# schema_mpb_1_1_COM.net
KiCad netlist of a schematic drawn in EAGLE
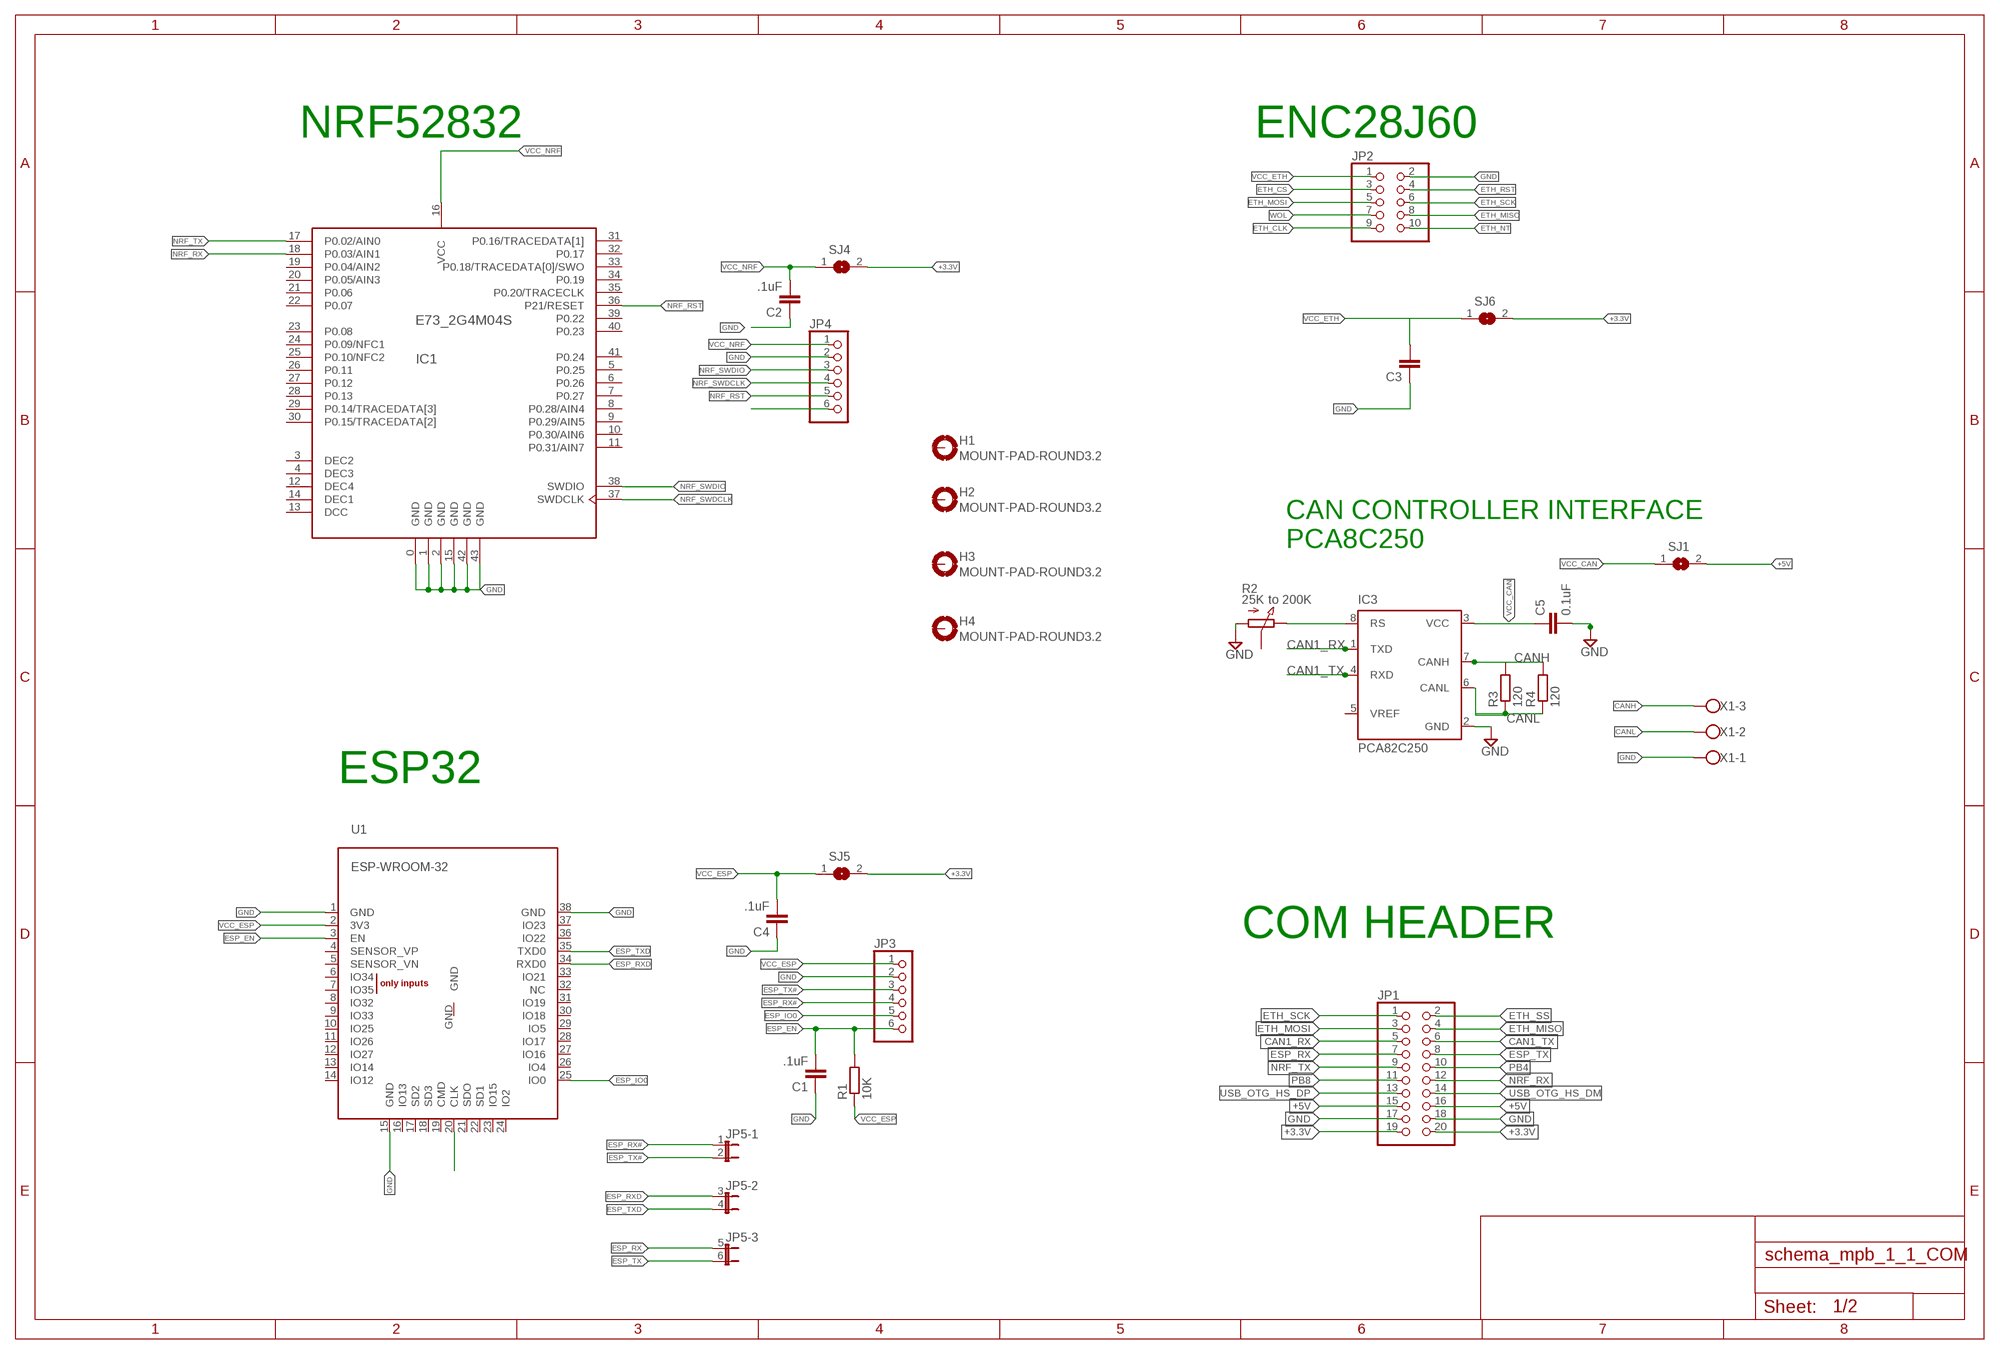
[diagram p0: schematic, sheet 1]

(export (version "E")
  (design (tool "Eeschema 10.0.6"))
  (components
    (comp (ref "C1")
      (value ".1uF")
      (footprint "eagle-import:C0603")
      (libsource (lib "eagle-import") (part "C-EUC0603"))
    )
    (comp (ref "C2")
      (value ".1uF")
      (footprint "eagle-import:C0603")
      (libsource (lib "eagle-import") (part "C-EUC0603"))
    )
    (comp (ref "C3")
      (value "C-EUC0603")
      (footprint "eagle-import:C0603")
      (libsource (lib "eagle-import") (part "C-EUC0603"))
    )
    (comp (ref "C4")
      (value ".1uF")
      (footprint "eagle-import:C0603")
      (libsource (lib "eagle-import") (part "C-EUC0603"))
    )
    (comp (ref "C5")
      (value "0.1uF")
      (footprint "eagle-import:C0805")
      (libsource (lib "eagle-import") (part "C-EUC0805"))
    )
    (comp (ref "H1")
      (value "MOUNT-PAD-ROUND3.2")
      (footprint "eagle-import:3,2-PAD")
      (libsource (lib "eagle-import") (part "MOUNT-PAD-ROUND3.2"))
    )
    (comp (ref "H2")
      (value "MOUNT-PAD-ROUND3.2")
      (footprint "eagle-import:3,2-PAD")
      (libsource (lib "eagle-import") (part "MOUNT-PAD-ROUND3.2"))
    )
    (comp (ref "H3")
      (value "MOUNT-PAD-ROUND3.2")
      (footprint "eagle-import:3,2-PAD")
      (libsource (lib "eagle-import") (part "MOUNT-PAD-ROUND3.2"))
    )
    (comp (ref "H4")
      (value "MOUNT-PAD-ROUND3.2")
      (footprint "eagle-import:3,2-PAD")
      (libsource (lib "eagle-import") (part "MOUNT-PAD-ROUND3.2"))
    )
    (comp (ref "IC1")
      (value "E73_2G4M04S")
      (footprint "eagle-import:E73_2G4M04S")
      (libsource (lib "eagle-import") (part "E73_2G4M04S"))
    )
    (comp (ref "IC3")
      (value "PCA82C250")
      (footprint "eagle-import:DIL08")
      (libsource (lib "eagle-import") (part "PCA82C250"))
    )
    (comp (ref "JP1")
      (value "PINHD-2X10")
      (footprint "eagle-import:2X10")
      (libsource (lib "eagle-import") (part "PINHD-2X10"))
    )
    (comp (ref "JP2")
      (value "PINHD-2X5")
      (footprint "eagle-import:2X05")
      (libsource (lib "eagle-import") (part "PINHD-2X5"))
    )
    (comp (ref "JP3")
      (value "PINHD-1X6")
      (footprint "eagle-import:1X06")
      (libsource (lib "eagle-import") (part "PINHD-1X6"))
    )
    (comp (ref "JP4")
      (value "PINHD-1X6")
      (footprint "eagle-import:1X06")
      (libsource (lib "eagle-import") (part "PINHD-1X6"))
    )
    (comp (ref "JP5")
      (value "JP3QE")
      (footprint "eagle-import:JP3Q")
      (libsource (lib "eagle-import") (part "JP3QE"))
    )
    (comp (ref "R1")
      (value "10K")
      (footprint "eagle-import:R0603")
      (libsource (lib "eagle-import") (part "R-EU_R0603"))
    )
    (comp (ref "R2")
      (value "25K to 200K")
      (footprint "eagle-import:PC25")
      (fields (field (name "MF") "CLAROSTAT") (field (name "MPN") "308NPC25KS"))
      (libsource (lib "eagle-import") (part "PC25"))
    )
    (comp (ref "R3")
      (value "120")
      (footprint "eagle-import:R0805")
      (libsource (lib "eagle-import") (part "R-EU_R0805"))
    )
    (comp (ref "R4")
      (value "120")
      (footprint "eagle-import:R0805")
      (libsource (lib "eagle-import") (part "R-EU_R0805"))
    )
    (comp (ref "SJ1")
      (value "SJW")
      (footprint "eagle-import:SJW")
      (libsource (lib "eagle-import") (part "SJW"))
    )
    (comp (ref "SJ4")
      (value "SJW")
      (footprint "eagle-import:SJW")
      (libsource (lib "eagle-import") (part "SJW"))
    )
    (comp (ref "SJ5")
      (value "SJW")
      (footprint "eagle-import:SJW")
      (libsource (lib "eagle-import") (part "SJW"))
    )
    (comp (ref "SJ6")
      (value "SJW")
      (footprint "eagle-import:SJW")
      (libsource (lib "eagle-import") (part "SJW"))
    )
    (comp (ref "U1")
      (value "ESP-WROOM-32")
      (footprint "eagle-import:ESP-WROOM-32")
      (libsource (lib "eagle-import") (part "ESP-WROOM-32"))
    )
    (comp (ref "X1")
      (value "W237-103")
      (footprint "eagle-import:W237-103")
      (fields (field (name "MPN") "237-103"))
      (libsource (lib "eagle-import") (part "W237-103"))
    )
  )
  (nets
    (net (code "1") (name "+3.3V") (class "Default")
      (node (ref "JP1") (pin "19") (pinfunction "19_19") (pintype "passive"))
      (node (ref "JP1") (pin "20") (pinfunction "20_20") (pintype "passive"))
      (node (ref "SJ4") (pin "2") (pinfunction "2_2") (pintype "passive"))
      (node (ref "SJ5") (pin "2") (pinfunction "2_2") (pintype "passive"))
      (node (ref "SJ6") (pin "2") (pinfunction "2_2") (pintype "passive"))
    )
    (net (code "2") (name "+5V") (class "Default")
      (node (ref "JP1") (pin "15") (pinfunction "15_15") (pintype "passive"))
      (node (ref "JP1") (pin "16") (pinfunction "16_16") (pintype "passive"))
      (node (ref "SJ1") (pin "2") (pinfunction "2_2") (pintype "passive"))
    )
    (net (code "3") (name "CAN1_RX") (class "Default")
      (node (ref "IC3") (pin "1") (pinfunction "TXD_1") (pintype "input"))
      (node (ref "JP1") (pin "5") (pinfunction "5_5") (pintype "passive"))
    )
    (net (code "4") (name "CAN1_TX") (class "Default")
      (node (ref "IC3") (pin "4") (pinfunction "RXD_4") (pintype "output"))
      (node (ref "JP1") (pin "6") (pinfunction "6_6") (pintype "passive"))
    )
    (net (code "5") (name "CANH") (class "Default")
      (node (ref "IC3") (pin "7") (pinfunction "CANH_7") (pintype "bidirectional"))
      (node (ref "R3") (pin "2") (pinfunction "2_2") (pintype "passive"))
      (node (ref "R4") (pin "2") (pinfunction "2_2") (pintype "passive"))
      (node (ref "X1") (pin "3") (pinfunction "KL_3") (pintype "passive"))
    )
    (net (code "6") (name "CANL") (class "Default")
      (node (ref "IC3") (pin "6") (pinfunction "CANL_6") (pintype "bidirectional"))
      (node (ref "R3") (pin "1") (pinfunction "1_1") (pintype "passive"))
      (node (ref "R4") (pin "1") (pinfunction "1_1") (pintype "passive"))
      (node (ref "X1") (pin "2") (pinfunction "KL_2") (pintype "passive"))
    )
    (net (code "7") (name "DCC") (class "Default")
      (node (ref "IC1") (pin "13") (pinfunction "DCC_13") (pintype "power_in"))
    )
    (net (code "8") (name "DEC1") (class "Default")
      (node (ref "IC1") (pin "14") (pinfunction "DEC1_14") (pintype "power_in"))
    )
    (net (code "9") (name "DEC2") (class "Default")
      (node (ref "IC1") (pin "3") (pinfunction "DEC2_3") (pintype "power_in"))
    )
    (net (code "10") (name "DEC3") (class "Default")
      (node (ref "IC1") (pin "4") (pinfunction "DEC3_4") (pintype "power_in"))
    )
    (net (code "11") (name "DEC4") (class "Default")
      (node (ref "IC1") (pin "12") (pinfunction "DEC4_12") (pintype "power_in"))
    )
    (net (code "12") (name "ESP_EN") (class "Default")
      (node (ref "C1") (pin "2") (pinfunction "2_2") (pintype "passive"))
      (node (ref "JP3") (pin "6") (pinfunction "6_6") (pintype "passive"))
      (node (ref "R1") (pin "2") (pinfunction "2_2") (pintype "passive"))
      (node (ref "U1") (pin "3") (pinfunction "EN_3") (pintype "bidirectional"))
    )
    (net (code "13") (name "ESP_IO0") (class "Default")
      (node (ref "JP3") (pin "5") (pinfunction "5_5") (pintype "passive"))
      (node (ref "U1") (pin "25") (pinfunction "IO0_25") (pintype "bidirectional"))
    )
    (net (code "14") (name "ESP_RX") (class "Default")
      (node (ref "JP1") (pin "7") (pinfunction "7_7") (pintype "passive"))
      (node (ref "JP5") (pin "5") (pinfunction "1_5") (pintype "passive"))
    )
    (net (code "15") (name "ESP_RX#") (class "Default")
      (node (ref "JP3") (pin "4") (pinfunction "4_4") (pintype "passive"))
      (node (ref "JP5") (pin "1") (pinfunction "1_1") (pintype "passive"))
    )
    (net (code "16") (name "ESP_RXD") (class "Default")
      (node (ref "JP5") (pin "3") (pinfunction "1_3") (pintype "passive"))
      (node (ref "U1") (pin "34") (pinfunction "RXD0_34") (pintype "bidirectional"))
    )
    (net (code "17") (name "ESP_TX") (class "Default")
      (node (ref "JP1") (pin "8") (pinfunction "8_8") (pintype "passive"))
      (node (ref "JP5") (pin "6") (pinfunction "2_6") (pintype "passive"))
    )
    (net (code "18") (name "ESP_TX#") (class "Default")
      (node (ref "JP3") (pin "3") (pinfunction "3_3") (pintype "passive"))
      (node (ref "JP5") (pin "2") (pinfunction "2_2") (pintype "passive"))
    )
    (net (code "19") (name "ESP_TXD") (class "Default")
      (node (ref "JP5") (pin "4") (pinfunction "2_4") (pintype "passive"))
      (node (ref "U1") (pin "35") (pinfunction "TXD0_35") (pintype "bidirectional"))
    )
    (net (code "20") (name "ETH_CLK") (class "Default")
      (node (ref "JP2") (pin "9") (pinfunction "9_9") (pintype "passive"))
    )
    (net (code "21") (name "ETH_CS") (class "Default")
      (node (ref "JP2") (pin "3") (pinfunction "3_3") (pintype "passive"))
    )
    (net (code "22") (name "ETH_MISO") (class "Default")
      (node (ref "JP1") (pin "4") (pinfunction "4_4") (pintype "passive"))
      (node (ref "JP2") (pin "8") (pinfunction "8_8") (pintype "passive"))
    )
    (net (code "23") (name "ETH_MOSI") (class "Default")
      (node (ref "JP1") (pin "3") (pinfunction "3_3") (pintype "passive"))
      (node (ref "JP2") (pin "5") (pinfunction "5_5") (pintype "passive"))
    )
    (net (code "24") (name "ETH_NT") (class "Default")
      (node (ref "JP2") (pin "10") (pinfunction "10_10") (pintype "passive"))
    )
    (net (code "25") (name "ETH_RST") (class "Default")
      (node (ref "JP2") (pin "4") (pinfunction "4_4") (pintype "passive"))
    )
    (net (code "26") (name "ETH_SCK") (class "Default")
      (node (ref "JP1") (pin "1") (pinfunction "1_1") (pintype "passive"))
      (node (ref "JP2") (pin "6") (pinfunction "6_6") (pintype "passive"))
    )
    (net (code "27") (name "ETH_SS") (class "Default")
      (node (ref "JP1") (pin "2") (pinfunction "2_2") (pintype "passive"))
    )
    (net (code "28") (name "GND") (class "Default")
      (node (ref "C1") (pin "1") (pinfunction "1_1") (pintype "passive"))
      (node (ref "C2") (pin "1") (pinfunction "1_1") (pintype "passive"))
      (node (ref "C3") (pin "1") (pinfunction "1_1") (pintype "passive"))
      (node (ref "C4") (pin "1") (pinfunction "1_1") (pintype "passive"))
      (node (ref "C5") (pin "2") (pinfunction "2_2") (pintype "passive"))
      (node (ref "IC1") (pin "0") (pinfunction "GND_0") (pintype "bidirectional"))
      (node (ref "IC1") (pin "1") (pinfunction "GND_1") (pintype "bidirectional"))
      (node (ref "IC1") (pin "15") (pinfunction "GND_15") (pintype "bidirectional"))
      (node (ref "IC1") (pin "2") (pinfunction "GND_2") (pintype "bidirectional"))
      (node (ref "IC1") (pin "42") (pinfunction "GND_42") (pintype "bidirectional"))
      (node (ref "IC1") (pin "43") (pinfunction "GND_43") (pintype "bidirectional"))
      (node (ref "IC3") (pin "2") (pinfunction "GND_2") (pintype "power_in"))
      (node (ref "JP1") (pin "17") (pinfunction "17_17") (pintype "passive"))
      (node (ref "JP1") (pin "18") (pinfunction "18_18") (pintype "passive"))
      (node (ref "JP2") (pin "2") (pinfunction "2_2") (pintype "passive"))
      (node (ref "JP3") (pin "2") (pinfunction "2_2") (pintype "passive"))
      (node (ref "JP4") (pin "2") (pinfunction "2_2") (pintype "passive"))
      (node (ref "R2") (pin "A") (pinfunction "A_A") (pintype "passive"))
      (node (ref "U1") (pin "1") (pinfunction "GND_1") (pintype "bidirectional"))
      (node (ref "U1") (pin "15") (pinfunction "GND_15") (pintype "bidirectional"))
      (node (ref "U1") (pin "38") (pinfunction "GND_38") (pintype "bidirectional"))
      (node (ref "X1") (pin "1") (pinfunction "KL_1") (pintype "passive"))
    )
    (net (code "29") (name "NRF_RST") (class "Default")
      (node (ref "IC1") (pin "36") (pinfunction "P21/RESET_36") (pintype "bidirectional"))
      (node (ref "JP4") (pin "5") (pinfunction "5_5") (pintype "passive"))
    )
    (net (code "30") (name "NRF_RX") (class "Default")
      (node (ref "IC1") (pin "18") (pinfunction "P0.03/AIN1_18") (pintype "bidirectional"))
      (node (ref "JP1") (pin "12") (pinfunction "12_12") (pintype "passive"))
    )
    (net (code "31") (name "NRF_SWDCLK") (class "Default")
      (node (ref "IC1") (pin "37") (pinfunction "SWDCLK_37") (pintype "input"))
      (node (ref "JP4") (pin "4") (pinfunction "4_4") (pintype "passive"))
    )
    (net (code "32") (name "NRF_SWDIO") (class "Default")
      (node (ref "IC1") (pin "38") (pinfunction "SWDIO_38") (pintype "bidirectional"))
      (node (ref "JP4") (pin "3") (pinfunction "3_3") (pintype "passive"))
    )
    (net (code "33") (name "NRF_TX") (class "Default")
      (node (ref "IC1") (pin "17") (pinfunction "P0.02/AIN0_17") (pintype "bidirectional"))
      (node (ref "JP1") (pin "9") (pinfunction "9_9") (pintype "passive"))
    )
    (net (code "34") (name "Net-(IC3-RS)") (class "Default")
      (node (ref "IC3") (pin "8") (pinfunction "RS_8") (pintype "input"))
      (node (ref "R2") (pin "E") (pinfunction "E_E") (pintype "passive"))
    )
    (net (code "35") (name "PB4") (class "Default")
      (node (ref "JP1") (pin "10") (pinfunction "10_10") (pintype "passive"))
    )
    (net (code "36") (name "PB8") (class "Default")
      (node (ref "JP1") (pin "11") (pinfunction "11_11") (pintype "passive"))
    )
    (net (code "37") (name "USB_OTG_HS_DM") (class "Default")
      (node (ref "JP1") (pin "14") (pinfunction "14_14") (pintype "passive"))
    )
    (net (code "38") (name "USB_OTG_HS_DP") (class "Default")
      (node (ref "JP1") (pin "13") (pinfunction "13_13") (pintype "passive"))
    )
    (net (code "39") (name "VCC_CAN") (class "Default")
      (node (ref "C5") (pin "1") (pinfunction "1_1") (pintype "passive"))
      (node (ref "IC3") (pin "3") (pinfunction "VCC_3") (pintype "power_in"))
      (node (ref "SJ1") (pin "1") (pinfunction "1_1") (pintype "passive"))
    )
    (net (code "40") (name "VCC_ESP") (class "Default")
      (node (ref "C4") (pin "2") (pinfunction "2_2") (pintype "passive"))
      (node (ref "JP3") (pin "1") (pinfunction "1_1") (pintype "passive"))
      (node (ref "R1") (pin "1") (pinfunction "1_1") (pintype "passive"))
      (node (ref "SJ5") (pin "1") (pinfunction "1_1") (pintype "passive"))
      (node (ref "U1") (pin "2") (pinfunction "3V3_2") (pintype "bidirectional"))
    )
    (net (code "41") (name "VCC_ETH") (class "Default")
      (node (ref "C3") (pin "2") (pinfunction "2_2") (pintype "passive"))
      (node (ref "JP2") (pin "1") (pinfunction "1_1") (pintype "passive"))
      (node (ref "SJ6") (pin "1") (pinfunction "1_1") (pintype "passive"))
    )
    (net (code "42") (name "VCC_NRF") (class "Default")
      (node (ref "C2") (pin "2") (pinfunction "2_2") (pintype "passive"))
      (node (ref "IC1") (pin "16") (pinfunction "VCC_16") (pintype "passive"))
      (node (ref "JP4") (pin "1") (pinfunction "1_1") (pintype "passive"))
      (node (ref "SJ4") (pin "1") (pinfunction "1_1") (pintype "passive"))
    )
    (net (code "43") (name "WOL") (class "Default")
      (node (ref "JP2") (pin "7") (pinfunction "7_7") (pintype "passive"))
    )
    (net (code "44") (name "unconnected-(H1-MOUNT-PadB3,2)") (class "Default")
      (node (ref "H1") (pin "B3,2") (pinfunction "MOUNT_B3,2") (pintype "passive"))
    )
    (net (code "45") (name "unconnected-(H2-MOUNT-PadB3,2)") (class "Default")
      (node (ref "H2") (pin "B3,2") (pinfunction "MOUNT_B3,2") (pintype "passive"))
    )
    (net (code "46") (name "unconnected-(H3-MOUNT-PadB3,2)") (class "Default")
      (node (ref "H3") (pin "B3,2") (pinfunction "MOUNT_B3,2") (pintype "passive"))
    )
    (net (code "47") (name "unconnected-(H4-MOUNT-PadB3,2)") (class "Default")
      (node (ref "H4") (pin "B3,2") (pinfunction "MOUNT_B3,2") (pintype "passive"))
    )
    (net (code "48") (name "unconnected-(IC1-P0.04{slash}AIN2-Pad19)") (class "Default")
      (node (ref "IC1") (pin "19") (pinfunction "P0.04/AIN2_19") (pintype "bidirectional"))
    )
    (net (code "49") (name "unconnected-(IC1-P0.05{slash}AIN3-Pad20)") (class "Default")
      (node (ref "IC1") (pin "20") (pinfunction "P0.05/AIN3_20") (pintype "bidirectional"))
    )
    (net (code "50") (name "unconnected-(IC1-P0.06-Pad21)") (class "Default")
      (node (ref "IC1") (pin "21") (pinfunction "P0.06_21") (pintype "bidirectional"))
    )
    (net (code "51") (name "unconnected-(IC1-P0.07-Pad22)") (class "Default")
      (node (ref "IC1") (pin "22") (pinfunction "P0.07_22") (pintype "bidirectional"))
    )
    (net (code "52") (name "unconnected-(IC1-P0.08-Pad23)") (class "Default")
      (node (ref "IC1") (pin "23") (pinfunction "P0.08_23") (pintype "bidirectional"))
    )
    (net (code "53") (name "unconnected-(IC1-P0.09{slash}NFC1-Pad24)") (class "Default")
      (node (ref "IC1") (pin "24") (pinfunction "P0.09/NFC1_24") (pintype "bidirectional"))
    )
    (net (code "54") (name "unconnected-(IC1-P0.10{slash}NFC2-Pad25)") (class "Default")
      (node (ref "IC1") (pin "25") (pinfunction "P0.10/NFC2_25") (pintype "bidirectional"))
    )
    (net (code "55") (name "unconnected-(IC1-P0.11-Pad26)") (class "Default")
      (node (ref "IC1") (pin "26") (pinfunction "P0.11_26") (pintype "bidirectional"))
    )
    (net (code "56") (name "unconnected-(IC1-P0.12-Pad27)") (class "Default")
      (node (ref "IC1") (pin "27") (pinfunction "P0.12_27") (pintype "bidirectional"))
    )
    (net (code "57") (name "unconnected-(IC1-P0.13-Pad28)") (class "Default")
      (node (ref "IC1") (pin "28") (pinfunction "P0.13_28") (pintype "bidirectional"))
    )
    (net (code "58") (name "unconnected-(IC1-P0.14{slash}TRACEDATA[3]-Pad29)") (class "Default")
      (node (ref "IC1") (pin "29") (pinfunction "P0.14/TRACEDATA[3]_29") (pintype "bidirectional"))
    )
    (net (code "59") (name "unconnected-(IC1-P0.15{slash}TRACEDATA[2]-Pad30)") (class "Default")
      (node (ref "IC1") (pin "30") (pinfunction "P0.15/TRACEDATA[2]_30") (pintype "bidirectional"))
    )
    (net (code "60") (name "unconnected-(IC1-P0.16{slash}TRACEDATA[1]-Pad31)") (class "Default")
      (node (ref "IC1") (pin "31") (pinfunction "P0.16/TRACEDATA[1]_31") (pintype "bidirectional"))
    )
    (net (code "61") (name "unconnected-(IC1-P0.17-Pad32)") (class "Default")
      (node (ref "IC1") (pin "32") (pinfunction "P0.17_32") (pintype "bidirectional"))
    )
    (net (code "62") (name "unconnected-(IC1-P0.18{slash}TRACEDATA[0]{slash}SWO-Pad33)") (class "Default")
      (node (ref "IC1") (pin "33") (pinfunction "P0.18/TRACEDATA[0]/SWO_33") (pintype "bidirectional"))
    )
    (net (code "63") (name "unconnected-(IC1-P0.19-Pad34)") (class "Default")
      (node (ref "IC1") (pin "34") (pinfunction "P0.19_34") (pintype "bidirectional"))
    )
    (net (code "64") (name "unconnected-(IC1-P0.20{slash}TRACECLK-Pad35)") (class "Default")
      (node (ref "IC1") (pin "35") (pinfunction "P0.20/TRACECLK_35") (pintype "bidirectional"))
    )
    (net (code "65") (name "unconnected-(IC1-P0.22-Pad39)") (class "Default")
      (node (ref "IC1") (pin "39") (pinfunction "P0.22_39") (pintype "bidirectional"))
    )
    (net (code "66") (name "unconnected-(IC1-P0.23-Pad40)") (class "Default")
      (node (ref "IC1") (pin "40") (pinfunction "P0.23_40") (pintype "bidirectional"))
    )
    (net (code "67") (name "unconnected-(IC1-P0.24-Pad41)") (class "Default")
      (node (ref "IC1") (pin "41") (pinfunction "P0.24_41") (pintype "bidirectional"))
    )
    (net (code "68") (name "unconnected-(IC1-P0.25-Pad5)") (class "Default")
      (node (ref "IC1") (pin "5") (pinfunction "P0.25_5") (pintype "bidirectional"))
    )
    (net (code "69") (name "unconnected-(IC1-P0.26-Pad6)") (class "Default")
      (node (ref "IC1") (pin "6") (pinfunction "P0.26_6") (pintype "bidirectional"))
    )
    (net (code "70") (name "unconnected-(IC1-P0.27-Pad7)") (class "Default")
      (node (ref "IC1") (pin "7") (pinfunction "P0.27_7") (pintype "bidirectional"))
    )
    (net (code "71") (name "unconnected-(IC1-P0.28{slash}AIN4-Pad8)") (class "Default")
      (node (ref "IC1") (pin "8") (pinfunction "P0.28/AIN4_8") (pintype "bidirectional"))
    )
    (net (code "72") (name "unconnected-(IC1-P0.29{slash}AIN5-Pad9)") (class "Default")
      (node (ref "IC1") (pin "9") (pinfunction "P0.29/AIN5_9") (pintype "bidirectional"))
    )
    (net (code "73") (name "unconnected-(IC1-P0.30{slash}AIN6-Pad10)") (class "Default")
      (node (ref "IC1") (pin "10") (pinfunction "P0.30/AIN6_10") (pintype "bidirectional"))
    )
    (net (code "74") (name "unconnected-(IC1-P0.31{slash}AIN7-Pad11)") (class "Default")
      (node (ref "IC1") (pin "11") (pinfunction "P0.31/AIN7_11") (pintype "bidirectional"))
    )
    (net (code "75") (name "unconnected-(IC3-VREF-Pad5)") (class "Default")
      (node (ref "IC3") (pin "5") (pinfunction "VREF_5") (pintype "output"))
    )
    (net (code "76") (name "unconnected-(JP4-Pad6)") (class "Default")
      (node (ref "JP4") (pin "6") (pinfunction "6_6") (pintype "passive"))
    )
    (net (code "77") (name "unconnected-(R2-PadS)") (class "Default")
      (node (ref "R2") (pin "S") (pinfunction "S_S") (pintype "passive"))
    )
    (net (code "78") (name "unconnected-(U1-CLK-Pad20)") (class "Default")
      (node (ref "U1") (pin "20") (pinfunction "CLK_20") (pintype "bidirectional"))
    )
    (net (code "79") (name "unconnected-(U1-CMD-Pad19)") (class "Default")
      (node (ref "U1") (pin "19") (pinfunction "CMD_19") (pintype "bidirectional"))
    )
    (net (code "80") (name "unconnected-(U1-IO2-Pad24)") (class "Default")
      (node (ref "U1") (pin "24") (pinfunction "IO2_24") (pintype "bidirectional"))
    )
    (net (code "81") (name "unconnected-(U1-IO4-Pad26)") (class "Default")
      (node (ref "U1") (pin "26") (pinfunction "IO4_26") (pintype "bidirectional"))
    )
    (net (code "82") (name "unconnected-(U1-IO5-Pad29)") (class "Default")
      (node (ref "U1") (pin "29") (pinfunction "IO5_29") (pintype "bidirectional"))
    )
    (net (code "83") (name "unconnected-(U1-IO12-Pad14)") (class "Default")
      (node (ref "U1") (pin "14") (pinfunction "IO12_14") (pintype "bidirectional"))
    )
    (net (code "84") (name "unconnected-(U1-IO13-Pad16)") (class "Default")
      (node (ref "U1") (pin "16") (pinfunction "IO13_16") (pintype "bidirectional"))
    )
    (net (code "85") (name "unconnected-(U1-IO14-Pad13)") (class "Default")
      (node (ref "U1") (pin "13") (pinfunction "IO14_13") (pintype "bidirectional"))
    )
    (net (code "86") (name "unconnected-(U1-IO15-Pad23)") (class "Default")
      (node (ref "U1") (pin "23") (pinfunction "IO15_23") (pintype "bidirectional"))
    )
    (net (code "87") (name "unconnected-(U1-IO16-Pad27)") (class "Default")
      (node (ref "U1") (pin "27") (pinfunction "IO16_27") (pintype "bidirectional"))
    )
    (net (code "88") (name "unconnected-(U1-IO17-Pad28)") (class "Default")
      (node (ref "U1") (pin "28") (pinfunction "IO17_28") (pintype "bidirectional"))
    )
    (net (code "89") (name "unconnected-(U1-IO18-Pad30)") (class "Default")
      (node (ref "U1") (pin "30") (pinfunction "IO18_30") (pintype "bidirectional"))
    )
    (net (code "90") (name "unconnected-(U1-IO19-Pad31)") (class "Default")
      (node (ref "U1") (pin "31") (pinfunction "IO19_31") (pintype "bidirectional"))
    )
    (net (code "91") (name "unconnected-(U1-IO21-Pad33)") (class "Default")
      (node (ref "U1") (pin "33") (pinfunction "IO21_33") (pintype "bidirectional"))
    )
    (net (code "92") (name "unconnected-(U1-IO22-Pad36)") (class "Default")
      (node (ref "U1") (pin "36") (pinfunction "IO22_36") (pintype "bidirectional"))
    )
    (net (code "93") (name "unconnected-(U1-IO23-Pad37)") (class "Default")
      (node (ref "U1") (pin "37") (pinfunction "IO23_37") (pintype "bidirectional"))
    )
    (net (code "94") (name "unconnected-(U1-IO25-Pad10)") (class "Default")
      (node (ref "U1") (pin "10") (pinfunction "IO25_10") (pintype "bidirectional"))
    )
    (net (code "95") (name "unconnected-(U1-IO26-Pad11)") (class "Default")
      (node (ref "U1") (pin "11") (pinfunction "IO26_11") (pintype "bidirectional"))
    )
    (net (code "96") (name "unconnected-(U1-IO27-Pad12)") (class "Default")
      (node (ref "U1") (pin "12") (pinfunction "IO27_12") (pintype "bidirectional"))
    )
    (net (code "97") (name "unconnected-(U1-IO32-Pad8)") (class "Default")
      (node (ref "U1") (pin "8") (pinfunction "IO32_8") (pintype "bidirectional"))
    )
    (net (code "98") (name "unconnected-(U1-IO33-Pad9)") (class "Default")
      (node (ref "U1") (pin "9") (pinfunction "IO33_9") (pintype "bidirectional"))
    )
    (net (code "99") (name "unconnected-(U1-IO34-Pad6)") (class "Default")
      (node (ref "U1") (pin "6") (pinfunction "IO34_6") (pintype "input"))
    )
    (net (code "100") (name "unconnected-(U1-IO35-Pad7)") (class "Default")
      (node (ref "U1") (pin "7") (pinfunction "IO35_7") (pintype "input"))
    )
    (net (code "101") (name "unconnected-(U1-NC-Pad32)") (class "Default")
      (node (ref "U1") (pin "32") (pinfunction "NC_32") (pintype "bidirectional"))
    )
    (net (code "102") (name "unconnected-(U1-PadGND)") (class "Default")
      (node (ref "U1") (pin "GND") (pinfunction "GND_GND") (pintype "bidirectional"))
    )
    (net (code "103") (name "unconnected-(U1-SD1-Pad22)") (class "Default")
      (node (ref "U1") (pin "22") (pinfunction "SD1_22") (pintype "bidirectional"))
    )
    (net (code "104") (name "unconnected-(U1-SD2-Pad17)") (class "Default")
      (node (ref "U1") (pin "17") (pinfunction "SD2_17") (pintype "bidirectional"))
    )
    (net (code "105") (name "unconnected-(U1-SD3-Pad18)") (class "Default")
      (node (ref "U1") (pin "18") (pinfunction "SD3_18") (pintype "bidirectional"))
    )
    (net (code "106") (name "unconnected-(U1-SDO-Pad21)") (class "Default")
      (node (ref "U1") (pin "21") (pinfunction "SDO_21") (pintype "bidirectional"))
    )
    (net (code "107") (name "unconnected-(U1-SENSOR_VN-Pad5)") (class "Default")
      (node (ref "U1") (pin "5") (pinfunction "SENSOR_VN_5") (pintype "input"))
    )
    (net (code "108") (name "unconnected-(U1-SENSOR_VP-Pad4)") (class "Default")
      (node (ref "U1") (pin "4") (pinfunction "SENSOR_VP_4") (pintype "input"))
    )
  )
)
